# WiFi_Turnout_Controller_v2.net
KiCad netlist of a schematic drawn in EAGLE
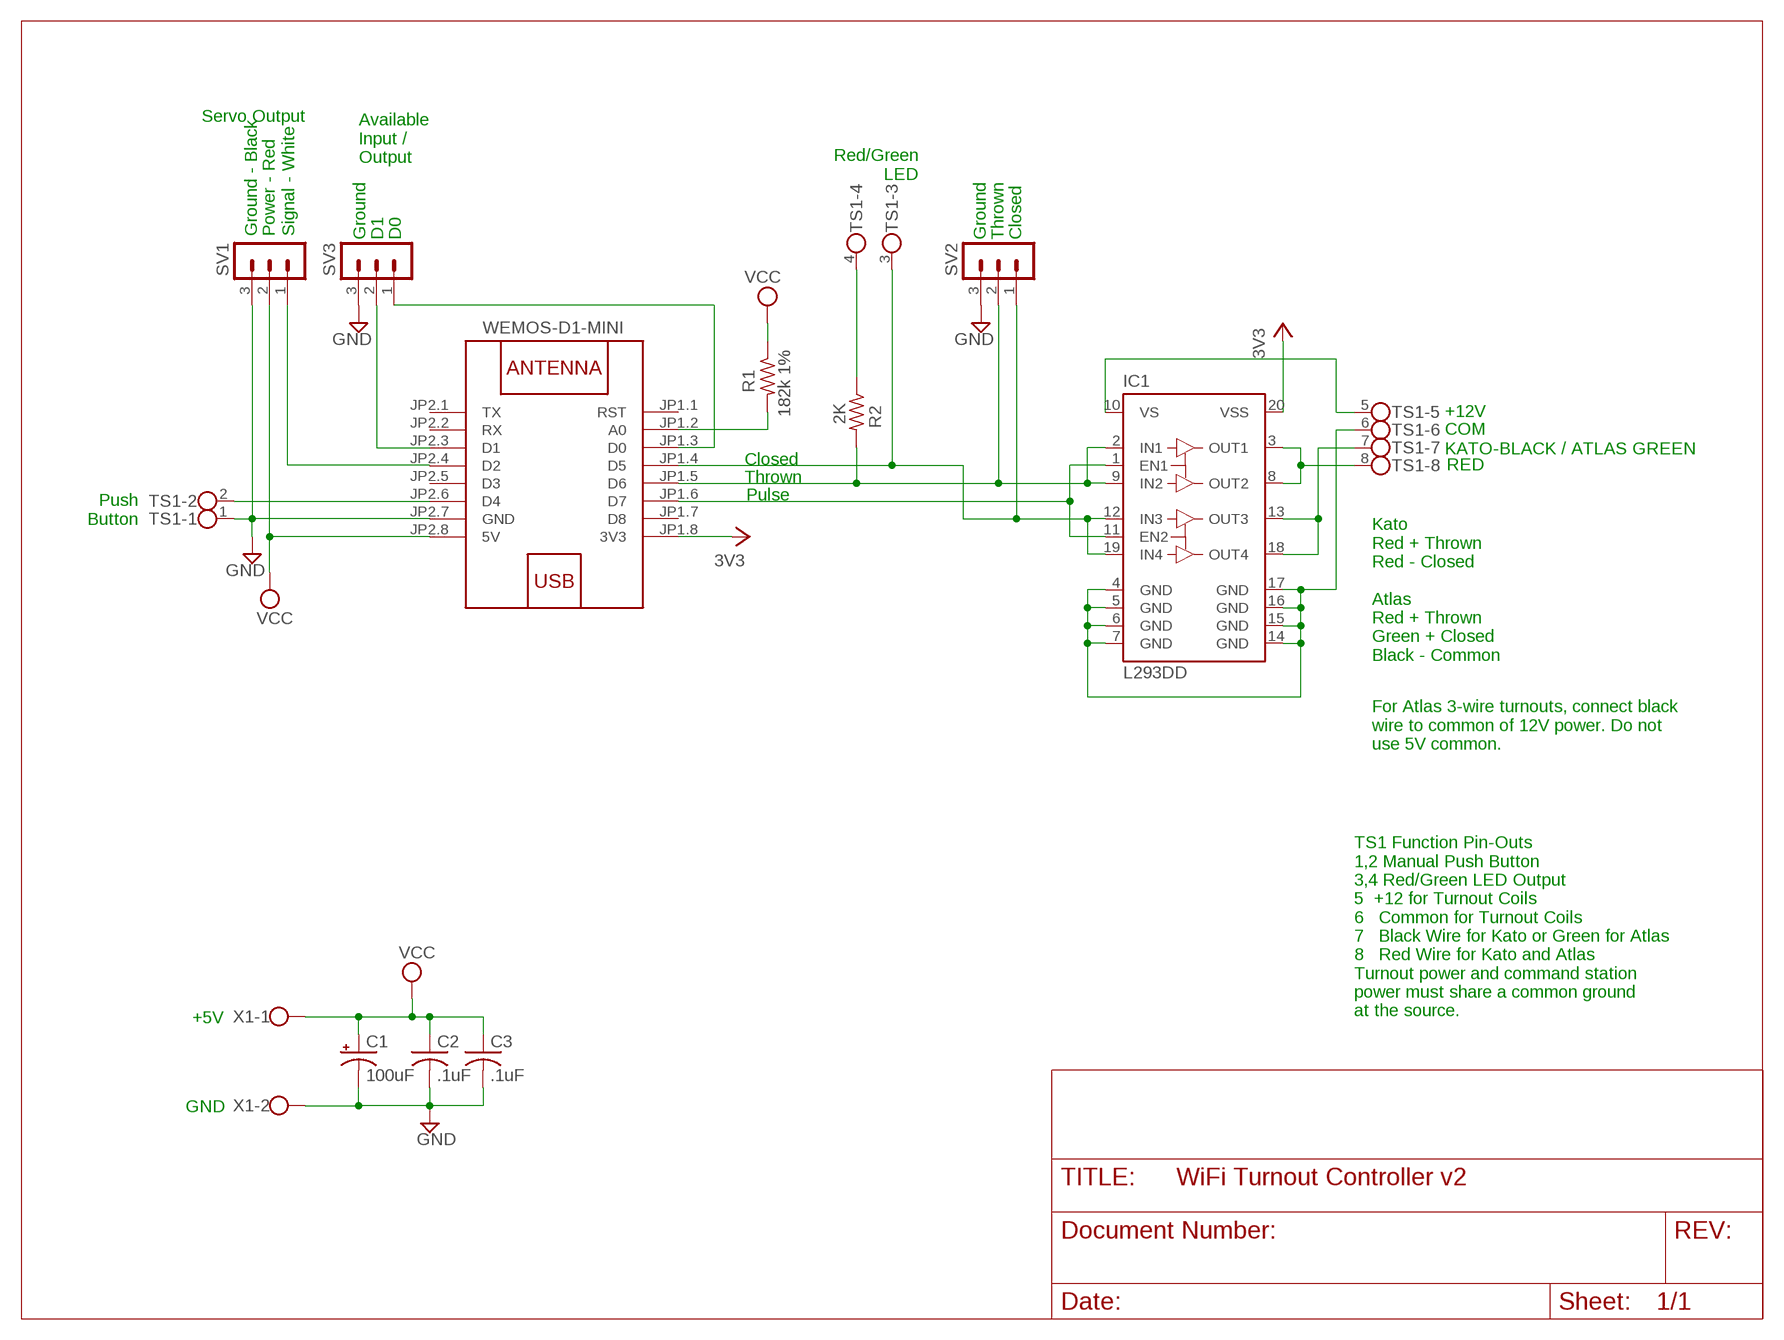
[diagram p0: schematic, sheet 1]

(export (version "E")
  (design (tool "Eeschema 10.0.6"))
  (components
    (comp (ref "C1")
      (value "100uF")
      (footprint "eagle-import:E3,5-8")
      (libsource (lib "eagle-import") (part "CPOL-USE3.5-8"))
    )
    (comp (ref "C2")
      (value ".1uF")
      (footprint "eagle-import:C1206")
      (libsource (lib "eagle-import") (part "C-USC1206"))
    )
    (comp (ref "C3")
      (value ".1uF")
      (footprint "eagle-import:C1206")
      (libsource (lib "eagle-import") (part "C-USC1206"))
    )
    (comp (ref "IC1")
      (value "L293DD")
      (footprint "eagle-import:SO20")
      (libsource (lib "eagle-import") (part "L293DD"))
    )
    (comp (ref "R1")
      (value "182k 1%")
      (footprint "eagle-import:R1206")
      (libsource (lib "eagle-import") (part "R-US_R1206"))
    )
    (comp (ref "R2")
      (value "2K")
      (footprint "eagle-import:R1206")
      (libsource (lib "eagle-import") (part "R-US_R1206"))
    )
    (comp (ref "SV1")
      (value "MA03-1")
      (footprint "eagle-import:MA03-1")
      (libsource (lib "eagle-import") (part "MA03-1"))
    )
    (comp (ref "SV2")
      (value "MA03-1")
      (footprint "eagle-import:MA03-1")
      (libsource (lib "eagle-import") (part "MA03-1"))
    )
    (comp (ref "SV3")
      (value "MA03-1")
      (footprint "eagle-import:MA03-1")
      (libsource (lib "eagle-import") (part "MA03-1"))
    )
    (comp (ref "TS1")
      (value "TERMBLK08")
      (footprint "eagle-import:08PB")
      (libsource (lib "eagle-import") (part "TERMBLK08"))
    )
    (comp (ref "U$1")
      (value "WEMOS-D1-MINI")
      (footprint "eagle-import:WEMOS-D1-MINI")
      (libsource (lib "eagle-import") (part "WEMOS-D1-MINI"))
    )
    (comp (ref "X1")
      (value "W237-102")
      (footprint "eagle-import:W237-102")
      (fields (field (name "MPN") "237-102"))
      (libsource (lib "eagle-import") (part "W237-102"))
    )
  )
  (nets
    (net (code "1") (name "3V3") (class "Default")
      (node (ref "IC1") (pin "20") (pinfunction "VSS_20") (pintype "power_in"))
      (node (ref "U$1") (pin "JP1.8") (pinfunction "3V3_JP1.8") (pintype "power_in"))
    )
    (net (code "2") (name "GND") (class "Default")
      (node (ref "C1") (pin "-") (pinfunction "-_-") (pintype "passive"))
      (node (ref "C2") (pin "2") (pinfunction "2_2") (pintype "passive"))
      (node (ref "C3") (pin "2") (pinfunction "2_2") (pintype "passive"))
      (node (ref "SV1") (pin "3") (pinfunction "3_3") (pintype "passive"))
      (node (ref "SV2") (pin "3") (pinfunction "3_3") (pintype "passive"))
      (node (ref "SV3") (pin "3") (pinfunction "3_3") (pintype "passive"))
      (node (ref "TS1") (pin "1") (pinfunction "1_1") (pintype "passive"))
      (node (ref "U$1") (pin "JP2.7") (pinfunction "GND_JP2.7") (pintype "power_in"))
      (node (ref "X1") (pin "2") (pinfunction "KL_2") (pintype "passive"))
    )
    (net (code "3") (name "Net-(IC1-EN1)") (class "Default")
      (node (ref "IC1") (pin "1") (pinfunction "EN1_1") (pintype "input"))
      (node (ref "IC1") (pin "11") (pinfunction "EN2_11") (pintype "input"))
      (node (ref "U$1") (pin "JP1.6") (pinfunction "D7_JP1.6") (pintype "bidirectional"))
    )
    (net (code "4") (name "Net-(IC1-IN1)") (class "Default")
      (node (ref "IC1") (pin "2") (pinfunction "IN1_2") (pintype "input"))
      (node (ref "IC1") (pin "9") (pinfunction "IN2_9") (pintype "input"))
      (node (ref "R2") (pin "2") (pinfunction "2_2") (pintype "passive"))
      (node (ref "SV2") (pin "2") (pinfunction "2_2") (pintype "passive"))
      (node (ref "U$1") (pin "JP1.5") (pinfunction "D6_JP1.5") (pintype "bidirectional"))
    )
    (net (code "5") (name "Net-(IC1-IN3)") (class "Default")
      (node (ref "IC1") (pin "12") (pinfunction "IN3_12") (pintype "input"))
      (node (ref "IC1") (pin "19") (pinfunction "IN4_19") (pintype "input"))
      (node (ref "SV2") (pin "1") (pinfunction "1_1") (pintype "passive"))
      (node (ref "TS1") (pin "3") (pinfunction "1_3") (pintype "passive"))
      (node (ref "U$1") (pin "JP1.4") (pinfunction "D5_JP1.4") (pintype "bidirectional"))
    )
    (net (code "6") (name "Net-(IC1-OUT1)") (class "Default")
      (node (ref "IC1") (pin "3") (pinfunction "OUT1_3") (pintype "output"))
      (node (ref "IC1") (pin "8") (pinfunction "OUT2_8") (pintype "output"))
      (node (ref "TS1") (pin "8") (pinfunction "1_8") (pintype "passive"))
    )
    (net (code "7") (name "Net-(IC1-OUT3)") (class "Default")
      (node (ref "IC1") (pin "13") (pinfunction "OUT3_13") (pintype "output"))
      (node (ref "IC1") (pin "18") (pinfunction "OUT4_18") (pintype "output"))
      (node (ref "TS1") (pin "7") (pinfunction "1_7") (pintype "passive"))
    )
    (net (code "8") (name "Net-(IC1-VS)") (class "Default")
      (node (ref "IC1") (pin "10") (pinfunction "VS_10") (pintype "power_in"))
      (node (ref "TS1") (pin "5") (pinfunction "1_5") (pintype "passive"))
    )
    (net (code "9") (name "Net-(TS1B-1)") (class "Default")
      (node (ref "TS1") (pin "2") (pinfunction "1_2") (pintype "passive"))
      (node (ref "U$1") (pin "JP2.6") (pinfunction "D4_JP2.6") (pintype "bidirectional"))
    )
    (net (code "10") (name "Net-(TS1D-1)") (class "Default")
      (node (ref "R2") (pin "1") (pinfunction "1_1") (pintype "passive"))
      (node (ref "TS1") (pin "4") (pinfunction "1_4") (pintype "passive"))
    )
    (net (code "11") (name "Net-(TS1F-1)") (class "Default")
      (node (ref "IC1") (pin "14") (pinfunction "GND_14") (pintype "power_in"))
      (node (ref "IC1") (pin "15") (pinfunction "GND_15") (pintype "power_in"))
      (node (ref "IC1") (pin "16") (pinfunction "GND_16") (pintype "power_in"))
      (node (ref "IC1") (pin "17") (pinfunction "GND_17") (pintype "power_in"))
      (node (ref "IC1") (pin "4") (pinfunction "GND_4") (pintype "power_in"))
      (node (ref "IC1") (pin "5") (pinfunction "GND_5") (pintype "power_in"))
      (node (ref "IC1") (pin "6") (pinfunction "GND_6") (pintype "power_in"))
      (node (ref "IC1") (pin "7") (pinfunction "GND_7") (pintype "power_in"))
      (node (ref "TS1") (pin "6") (pinfunction "1_6") (pintype "passive"))
    )
    (net (code "12") (name "Net-(U$1-A0)") (class "Default")
      (node (ref "R1") (pin "2") (pinfunction "2_2") (pintype "passive"))
      (node (ref "U$1") (pin "JP1.2") (pinfunction "A0_JP1.2") (pintype "bidirectional"))
    )
    (net (code "13") (name "Net-(U$1-D0)") (class "Default")
      (node (ref "SV3") (pin "1") (pinfunction "1_1") (pintype "passive"))
      (node (ref "U$1") (pin "JP1.3") (pinfunction "D0_JP1.3") (pintype "bidirectional"))
    )
    (net (code "14") (name "Net-(U$1-D1)") (class "Default")
      (node (ref "SV3") (pin "2") (pinfunction "2_2") (pintype "passive"))
      (node (ref "U$1") (pin "JP2.3") (pinfunction "D1_JP2.3") (pintype "bidirectional"))
    )
    (net (code "15") (name "Net-(U$1-D2)") (class "Default")
      (node (ref "SV1") (pin "1") (pinfunction "1_1") (pintype "passive"))
      (node (ref "U$1") (pin "JP2.4") (pinfunction "D2_JP2.4") (pintype "bidirectional"))
    )
    (net (code "16") (name "VCC") (class "Default")
      (node (ref "C1") (pin "+") (pinfunction "+_+") (pintype "passive"))
      (node (ref "C2") (pin "1") (pinfunction "1_1") (pintype "passive"))
      (node (ref "C3") (pin "1") (pinfunction "1_1") (pintype "passive"))
      (node (ref "R1") (pin "1") (pinfunction "1_1") (pintype "passive"))
      (node (ref "SV1") (pin "2") (pinfunction "2_2") (pintype "passive"))
      (node (ref "U$1") (pin "JP2.8") (pinfunction "5V_JP2.8") (pintype "power_in"))
      (node (ref "X1") (pin "1") (pinfunction "KL_1") (pintype "passive"))
    )
    (net (code "17") (name "unconnected-(U$1-D3-PadJP2.5)") (class "Default")
      (node (ref "U$1") (pin "JP2.5") (pinfunction "D3_JP2.5") (pintype "bidirectional"))
    )
    (net (code "18") (name "unconnected-(U$1-D8-PadJP1.7)") (class "Default")
      (node (ref "U$1") (pin "JP1.7") (pinfunction "D8_JP1.7") (pintype "bidirectional"))
    )
    (net (code "19") (name "unconnected-(U$1-RST-PadJP1.1)") (class "Default")
      (node (ref "U$1") (pin "JP1.1") (pinfunction "RST_JP1.1") (pintype "bidirectional"))
    )
    (net (code "20") (name "unconnected-(U$1-RX-PadJP2.2)") (class "Default")
      (node (ref "U$1") (pin "JP2.2") (pinfunction "RX_JP2.2") (pintype "bidirectional"))
    )
    (net (code "21") (name "unconnected-(U$1-TX-PadJP2.1)") (class "Default")
      (node (ref "U$1") (pin "JP2.1") (pinfunction "TX_JP2.1") (pintype "bidirectional"))
    )
  )
)
